# controller.net
KiCad netlist of a schematic drawn in EAGLE
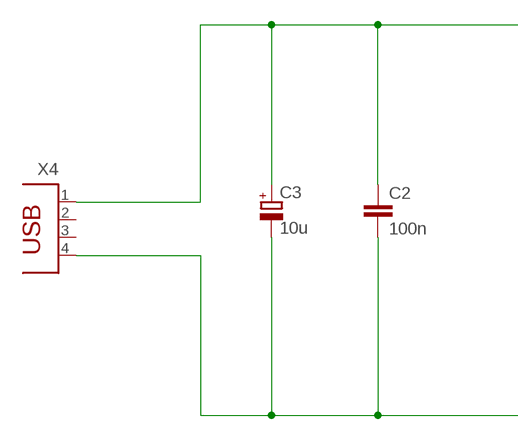
[diagram p0: schematic, sheet 1, part 1 of 2]
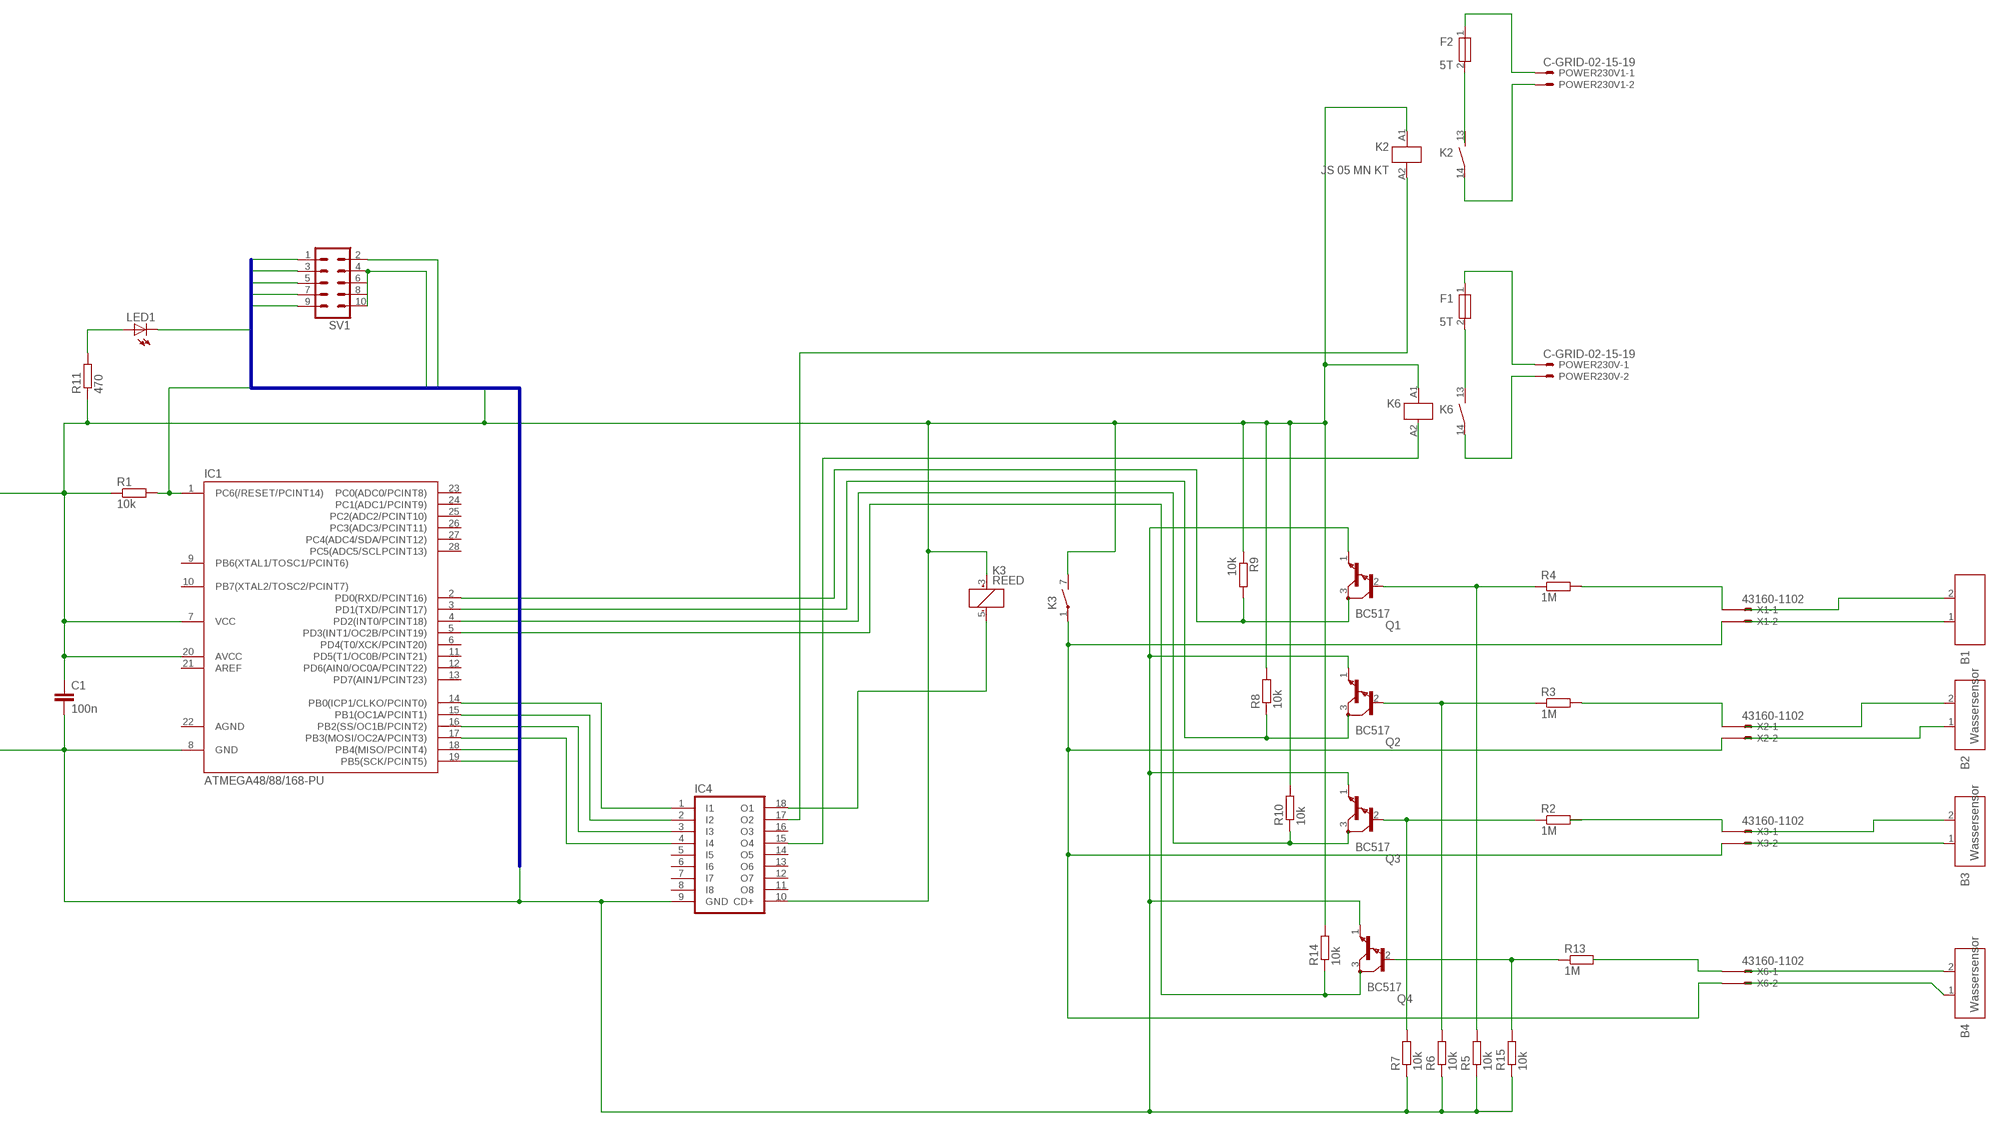
[diagram p1: schematic, sheet 1, part 2 of 2]

(export (version "E")
  (design (tool "Eeschema 10.0.6"))
  (components
    (comp (ref "B1")
      (value "MESSFUEHLER_2")
      (footprint "eagle-import:MESSFUEHLER_2")
      (fields (field (name "FUNKTION") "Wassersensor"))
      (libsource (lib "eagle-import") (part "MESSFUEHLER_2"))
    )
    (comp (ref "B2")
      (value "MESSFUEHLER_2")
      (footprint "eagle-import:MESSFUEHLER_2")
      (fields (field (name "FUNKTION") "Wassersensor"))
      (libsource (lib "eagle-import") (part "MESSFUEHLER_2"))
    )
    (comp (ref "B3")
      (value "MESSFUEHLER_2")
      (footprint "eagle-import:MESSFUEHLER_2")
      (fields (field (name "FUNKTION") "Wassersensor"))
      (libsource (lib "eagle-import") (part "MESSFUEHLER_2"))
    )
    (comp (ref "B4")
      (value "MESSFUEHLER_2")
      (footprint "eagle-import:MESSFUEHLER_2")
      (fields (field (name "FUNKTION") "Wassersensor"))
      (libsource (lib "eagle-import") (part "MESSFUEHLER_2"))
    )
    (comp (ref "C1")
      (value "100n")
      (footprint "eagle-import:C025-025X050")
      (libsource (lib "eagle-import") (part "C-EU025-025X050"))
    )
    (comp (ref "C2")
      (value "100n")
      (footprint "eagle-import:C025-030X050")
      (libsource (lib "eagle-import") (part "C-EU025-030X050"))
    )
    (comp (ref "C3")
      (value "10u")
      (footprint "eagle-import:E2,5-7")
      (libsource (lib "eagle-import") (part "CPOL-EUE2.5-7"))
    )
    (comp (ref "F1")
      (value "SICHERUNG_1-POL")
      (footprint "eagle-import:SICHERUNG_1-POL")
      (fields (field (name "TYPE") "5T"))
      (libsource (lib "eagle-import") (part "SICHERUNG_1-POL"))
    )
    (comp (ref "F2")
      (value "SICHERUNG_1-POL")
      (footprint "eagle-import:SICHERUNG_1-POL")
      (fields (field (name "TYPE") "5T"))
      (libsource (lib "eagle-import") (part "SICHERUNG_1-POL"))
    )
    (comp (ref "IC1")
      (value "ATMEGA48/88/168-PU")
      (footprint "eagle-import:DIL28-3")
      (libsource (lib "eagle-import") (part "ATMEGA48/88/168-PU"))
    )
    (comp (ref "IC4")
      (value "ULN2803A")
      (footprint "eagle-import:DIL18")
      (libsource (lib "eagle-import") (part "ULN2803A"))
    )
    (comp (ref "K2")
      (value "HILFSSCHUETZ_13-14")
      (footprint "eagle-import:HILFSSCHUETZ_13-14")
      (fields (field (name "TYPE") "JS 05 MN KT"))
      (libsource (lib "eagle-import") (part "HILFSSCHUETZ_13-14"))
    )
    (comp (ref "K3")
      (value "REED")
      (footprint "eagle-import:REED")
      (libsource (lib "eagle-import") (part "REED"))
    )
    (comp (ref "K6")
      (value "HILFSSCHUETZ_13-14")
      (footprint "eagle-import:HILFSSCHUETZ_13-14")
      (fields (field (name "TYPE") "JS 05 MN KT"))
      (libsource (lib "eagle-import") (part "HILFSSCHUETZ_13-14"))
    )
    (comp (ref "LED1")
      (value "LED5MM")
      (footprint "eagle-import:LED5MM")
      (libsource (lib "eagle-import") (part "LED5MM"))
    )
    (comp (ref "POWER230V")
      (value "C-GRID-02-15-19")
      (footprint "eagle-import:15-91-02")
      (libsource (lib "eagle-import") (part "C-GRID-02-15-19"))
    )
    (comp (ref "POWER230V1")
      (value "C-GRID-02-15-19")
      (footprint "eagle-import:15-91-02")
      (libsource (lib "eagle-import") (part "C-GRID-02-15-19"))
    )
    (comp (ref "Q1")
      (value "BC517")
      (footprint "eagle-import:TO92")
      (libsource (lib "eagle-import") (part "BC517"))
    )
    (comp (ref "Q2")
      (value "BC517")
      (footprint "eagle-import:TO92")
      (libsource (lib "eagle-import") (part "BC517"))
    )
    (comp (ref "Q3")
      (value "BC517")
      (footprint "eagle-import:TO92")
      (libsource (lib "eagle-import") (part "BC517"))
    )
    (comp (ref "Q4")
      (value "BC517")
      (footprint "eagle-import:TO92")
      (libsource (lib "eagle-import") (part "BC517"))
    )
    (comp (ref "R1")
      (value "10k")
      (footprint "eagle-import:0204_7")
      (libsource (lib "eagle-import") (part "R-EU_0204/7"))
    )
    (comp (ref "R2")
      (value "1M")
      (footprint "eagle-import:0204_7")
      (libsource (lib "eagle-import") (part "R-EU_0204/7"))
    )
    (comp (ref "R3")
      (value "1M")
      (footprint "eagle-import:0204_7")
      (libsource (lib "eagle-import") (part "R-EU_0204/7"))
    )
    (comp (ref "R4")
      (value "1M")
      (footprint "eagle-import:0204_7")
      (libsource (lib "eagle-import") (part "R-EU_0204/7"))
    )
    (comp (ref "R5")
      (value "10k")
      (footprint "eagle-import:0204_7")
      (libsource (lib "eagle-import") (part "R-EU_0204/7"))
    )
    (comp (ref "R6")
      (value "10k")
      (footprint "eagle-import:0204_7")
      (libsource (lib "eagle-import") (part "R-EU_0204/7"))
    )
    (comp (ref "R7")
      (value "10k")
      (footprint "eagle-import:0204_7")
      (libsource (lib "eagle-import") (part "R-EU_0204/7"))
    )
    (comp (ref "R8")
      (value "10k")
      (footprint "eagle-import:0204_7")
      (libsource (lib "eagle-import") (part "R-EU_0204/7"))
    )
    (comp (ref "R9")
      (value "10k")
      (footprint "eagle-import:0204_7")
      (libsource (lib "eagle-import") (part "R-EU_0204/7"))
    )
    (comp (ref "R10")
      (value "10k")
      (footprint "eagle-import:0204_7")
      (libsource (lib "eagle-import") (part "R-EU_0204/7"))
    )
    (comp (ref "R11")
      (value "470")
      (footprint "eagle-import:0204_7")
      (libsource (lib "eagle-import") (part "R-EU_0204/7"))
    )
    (comp (ref "R13")
      (value "1M")
      (footprint "eagle-import:0204_7")
      (libsource (lib "eagle-import") (part "R-EU_0204/7"))
    )
    (comp (ref "R14")
      (value "10k")
      (footprint "eagle-import:0204_7")
      (libsource (lib "eagle-import") (part "R-EU_0204/7"))
    )
    (comp (ref "R15")
      (value "10k")
      (footprint "eagle-import:0204_7")
      (libsource (lib "eagle-import") (part "R-EU_0204/7"))
    )
    (comp (ref "SV1")
      (value "MA05-2")
      (footprint "eagle-import:MA05-2")
      (libsource (lib "eagle-import") (part "MA05-2"))
    )
    (comp (ref "X1")
      (value "43160-1102")
      (footprint "eagle-import:43160-XX02")
      (fields (field (name "MF") "WALDOM/MOLEX"))
      (libsource (lib "eagle-import") (part "43160-0211"))
    )
    (comp (ref "X2")
      (value "43160-1102")
      (footprint "eagle-import:43160-XX02")
      (fields (field (name "MF") "WALDOM/MOLEX"))
      (libsource (lib "eagle-import") (part "43160-0211"))
    )
    (comp (ref "X3")
      (value "43160-1102")
      (footprint "eagle-import:43160-XX02")
      (fields (field (name "MF") "WALDOM/MOLEX"))
      (libsource (lib "eagle-import") (part "43160-0211"))
    )
    (comp (ref "X4")
      (value "PN87520")
      (footprint "eagle-import:PN87520")
      (libsource (lib "eagle-import") (part "PN87520"))
    )
    (comp (ref "X6")
      (value "43160-1102")
      (footprint "eagle-import:43160-XX02")
      (fields (field (name "MF") "WALDOM/MOLEX"))
      (libsource (lib "eagle-import") (part "43160-0211"))
    )
  )
  (nets
    (net (code "1") (name "/AGND") (class "Default")
      (node (ref "IC1") (pin "22") (pinfunction "AGND_22") (pintype "power_in"))
    )
    (net (code "2") (name "/GND") (class "Default")
      (node (ref "C1") (pin "2") (pinfunction "2_2") (pintype "passive"))
      (node (ref "C2") (pin "2") (pinfunction "2_2") (pintype "passive"))
      (node (ref "C3") (pin "-") (pinfunction "-_-") (pintype "passive"))
      (node (ref "IC1") (pin "8") (pinfunction "GND_8") (pintype "power_in"))
      (node (ref "IC4") (pin "9") (pinfunction "GND_9") (pintype "power_in"))
      (node (ref "Q1") (pin "1") (pinfunction "E_1") (pintype "passive"))
      (node (ref "Q2") (pin "1") (pinfunction "E_1") (pintype "passive"))
      (node (ref "Q3") (pin "1") (pinfunction "E_1") (pintype "passive"))
      (node (ref "Q4") (pin "1") (pinfunction "E_1") (pintype "passive"))
      (node (ref "R15") (pin "1") (pinfunction "1_1") (pintype "passive"))
      (node (ref "R5") (pin "1") (pinfunction "1_1") (pintype "passive"))
      (node (ref "R6") (pin "1") (pinfunction "1_1") (pintype "passive"))
      (node (ref "R7") (pin "1") (pinfunction "1_1") (pintype "passive"))
      (node (ref "SV1") (pin "10") (pinfunction "10_10") (pintype "passive"))
      (node (ref "SV1") (pin "2") (pinfunction "2_2") (pintype "passive"))
      (node (ref "SV1") (pin "4") (pinfunction "4_4") (pintype "passive"))
      (node (ref "X4") (pin "4") (pinfunction "4_4") (pintype "passive"))
    )
    (net (code "3") (name "/LED") (class "Default")
      (node (ref "LED1") (pin "K") (pinfunction "C_K") (pintype "passive"))
      (node (ref "SV1") (pin "3") (pinfunction "3_3") (pintype "passive"))
    )
    (net (code "4") (name "/MISO") (class "Default")
      (node (ref "IC1") (pin "18") (pinfunction "PB4(MISO/PCINT4)_18") (pintype "bidirectional"))
      (node (ref "SV1") (pin "9") (pinfunction "9_9") (pintype "passive"))
    )
    (net (code "5") (name "/MOSI") (class "Default")
      (node (ref "IC1") (pin "17") (pinfunction "PB3(MOSI/OC2A/PCINT3)_17") (pintype "bidirectional"))
      (node (ref "IC4") (pin "4") (pinfunction "I4_4") (pintype "input"))
      (node (ref "SV1") (pin "1") (pinfunction "1_1") (pintype "passive"))
    )
    (net (code "6") (name "/RESET") (class "Default")
      (node (ref "IC1") (pin "1") (pinfunction "PC6(/RESET/PCINT14)_1") (pintype "bidirectional"))
      (node (ref "R1") (pin "2") (pinfunction "2_2") (pintype "passive"))
      (node (ref "SV1") (pin "5") (pinfunction "5_5") (pintype "passive"))
    )
    (net (code "7") (name "/SCK") (class "Default")
      (node (ref "IC1") (pin "19") (pinfunction "PB5(SCK/PCINT5)_19") (pintype "bidirectional"))
      (node (ref "SV1") (pin "7") (pinfunction "7_7") (pintype "passive"))
    )
    (net (code "8") (name "Net-(IC1-AVCC)") (class "Default")
      (node (ref "C1") (pin "1") (pinfunction "1_1") (pintype "passive"))
      (node (ref "C2") (pin "1") (pinfunction "1_1") (pintype "passive"))
      (node (ref "C3") (pin "+") (pinfunction "+_+") (pintype "passive"))
      (node (ref "IC1") (pin "20") (pinfunction "AVCC_20") (pintype "passive"))
      (node (ref "IC1") (pin "7") (pinfunction "VCC_7") (pintype "power_in"))
      (node (ref "IC4") (pin "10") (pinfunction "CD+_10") (pintype "passive"))
      (node (ref "K2") (pin "A1") (pinfunction "A1_A1") (pintype "input"))
      (node (ref "K3") (pin "3") (pinfunction "+_3") (pintype "passive"))
      (node (ref "K3") (pin "7") (pinfunction "S_7") (pintype "passive"))
      (node (ref "K6") (pin "A1") (pinfunction "A1_A1") (pintype "input"))
      (node (ref "R1") (pin "1") (pinfunction "1_1") (pintype "passive"))
      (node (ref "R10") (pin "2") (pinfunction "2_2") (pintype "passive"))
      (node (ref "R11") (pin "1") (pinfunction "1_1") (pintype "passive"))
      (node (ref "R14") (pin "2") (pinfunction "2_2") (pintype "passive"))
      (node (ref "R8") (pin "2") (pinfunction "2_2") (pintype "passive"))
      (node (ref "R9") (pin "1") (pinfunction "1_1") (pintype "passive"))
      (node (ref "X4") (pin "1") (pinfunction "1_1") (pintype "passive"))
    )
    (net (code "9") (name "Net-(IC1-PB0(ICP1{slash}CLKO{slash}PCINT0))") (class "Default")
      (node (ref "IC1") (pin "14") (pinfunction "PB0(ICP1/CLKO/PCINT0)_14") (pintype "bidirectional"))
      (node (ref "IC4") (pin "1") (pinfunction "I1_1") (pintype "input"))
    )
    (net (code "10") (name "Net-(IC1-PB1(OC1A{slash}PCINT1))") (class "Default")
      (node (ref "IC1") (pin "15") (pinfunction "PB1(OC1A/PCINT1)_15") (pintype "bidirectional"))
      (node (ref "IC4") (pin "2") (pinfunction "I2_2") (pintype "input"))
    )
    (net (code "11") (name "Net-(IC1-PB2(SS{slash}OC1B{slash}PCINT2))") (class "Default")
      (node (ref "IC1") (pin "16") (pinfunction "PB2(SS/OC1B/PCINT2)_16") (pintype "bidirectional"))
      (node (ref "IC4") (pin "3") (pinfunction "I3_3") (pintype "input"))
    )
    (net (code "12") (name "Net-(IC1-PD0(RXD{slash}PCINT16))") (class "Default")
      (node (ref "IC1") (pin "2") (pinfunction "PD0(RXD/PCINT16)_2") (pintype "bidirectional"))
      (node (ref "Q1") (pin "3") (pinfunction "C_3") (pintype "passive"))
      (node (ref "R9") (pin "2") (pinfunction "2_2") (pintype "passive"))
    )
    (net (code "13") (name "Net-(IC1-PD1(TXD{slash}PCINT17))") (class "Default")
      (node (ref "IC1") (pin "3") (pinfunction "PD1(TXD/PCINT17)_3") (pintype "bidirectional"))
      (node (ref "Q2") (pin "3") (pinfunction "C_3") (pintype "passive"))
      (node (ref "R8") (pin "1") (pinfunction "1_1") (pintype "passive"))
    )
    (net (code "14") (name "Net-(IC1-PD2(INT0{slash}PCINT18))") (class "Default")
      (node (ref "IC1") (pin "4") (pinfunction "PD2(INT0/PCINT18)_4") (pintype "bidirectional"))
      (node (ref "Q3") (pin "3") (pinfunction "C_3") (pintype "passive"))
      (node (ref "R10") (pin "1") (pinfunction "1_1") (pintype "passive"))
    )
    (net (code "15") (name "Net-(IC1-PD3(INT1{slash}OC2B{slash}PCINT19))") (class "Default")
      (node (ref "IC1") (pin "5") (pinfunction "PD3(INT1/OC2B/PCINT19)_5") (pintype "bidirectional"))
      (node (ref "Q4") (pin "3") (pinfunction "C_3") (pintype "passive"))
      (node (ref "R14") (pin "1") (pinfunction "1_1") (pintype "passive"))
    )
    (net (code "16") (name "Net-(IC4-O1)") (class "Default")
      (node (ref "IC4") (pin "18") (pinfunction "O1_18") (pintype "open_collector"))
      (node (ref "K3") (pin "5") (pinfunction "-_5") (pintype "passive"))
    )
    (net (code "17") (name "Net-(IC4-O2)") (class "Default")
      (node (ref "IC4") (pin "17") (pinfunction "O2_17") (pintype "open_collector"))
      (node (ref "K2") (pin "A2") (pinfunction "A2_A2") (pintype "input"))
    )
    (net (code "18") (name "Net-(K2A-4)") (class "Default")
      (node (ref "K2") (pin "14") (pinfunction "4_14") (pintype "passive"))
      (node (ref "POWER230V1") (pin "2") (pinfunction "S_2") (pintype "passive"))
    )
    (net (code "19") (name "Net-(K3B-P)") (class "Default")
      (node (ref "K3") (pin "1") (pinfunction "P_1") (pintype "passive"))
      (node (ref "X1") (pin "2@1") (pinfunction "S_2@1") (pintype "passive"))
      (node (ref "X2") (pin "2@1") (pinfunction "S_2@1") (pintype "passive"))
      (node (ref "X3") (pin "2@1") (pinfunction "S_2@1") (pintype "passive"))
      (node (ref "X6") (pin "2@1") (pinfunction "S_2@1") (pintype "passive"))
    )
    (net (code "20") (name "Net-(K6A-3)") (class "Default")
      (node (ref "F1") (pin "2") (pinfunction "2_2") (pintype "passive"))
      (node (ref "K6") (pin "13") (pinfunction "3_13") (pintype "passive"))
    )
    (net (code "21") (name "Net-(K6A-4)") (class "Default")
      (node (ref "K6") (pin "14") (pinfunction "4_14") (pintype "passive"))
      (node (ref "POWER230V") (pin "2") (pinfunction "S_2") (pintype "passive"))
    )
    (net (code "22") (name "Net-(LED1-PadA)") (class "Default")
      (node (ref "LED1") (pin "A") (pinfunction "A_A") (pintype "passive"))
      (node (ref "R11") (pin "2") (pinfunction "2_2") (pintype "passive"))
    )
    (net (code "23") (name "Net-(POWER230V1A-S)") (class "Default")
      (node (ref "F2") (pin "1") (pinfunction "1_1") (pintype "passive"))
      (node (ref "POWER230V1") (pin "1") (pinfunction "S_1") (pintype "passive"))
    )
    (net (code "24") (name "Net-(POWER230VA-S)") (class "Default")
      (node (ref "F1") (pin "1") (pinfunction "1_1") (pintype "passive"))
      (node (ref "POWER230V") (pin "1") (pinfunction "S_1") (pintype "passive"))
    )
    (net (code "25") (name "Net-(Q1-B)") (class "Default")
      (node (ref "Q1") (pin "2") (pinfunction "B_2") (pintype "passive"))
      (node (ref "R4") (pin "1") (pinfunction "1_1") (pintype "passive"))
      (node (ref "R5") (pin "2") (pinfunction "2_2") (pintype "passive"))
    )
    (net (code "26") (name "Net-(Q2-B)") (class "Default")
      (node (ref "Q2") (pin "2") (pinfunction "B_2") (pintype "passive"))
      (node (ref "R3") (pin "1") (pinfunction "1_1") (pintype "passive"))
      (node (ref "R6") (pin "2") (pinfunction "2_2") (pintype "passive"))
    )
    (net (code "27") (name "Net-(Q3-B)") (class "Default")
      (node (ref "Q3") (pin "2") (pinfunction "B_2") (pintype "passive"))
      (node (ref "R2") (pin "1") (pinfunction "1_1") (pintype "passive"))
      (node (ref "R7") (pin "2") (pinfunction "2_2") (pintype "passive"))
    )
    (net (code "28") (name "Net-(Q4-B)") (class "Default")
      (node (ref "Q4") (pin "2") (pinfunction "B_2") (pintype "passive"))
      (node (ref "R13") (pin "1") (pinfunction "1_1") (pintype "passive"))
      (node (ref "R15") (pin "2") (pinfunction "2_2") (pintype "passive"))
    )
    (net (code "29") (name "Net-(R2-Pad2)") (class "Default")
      (node (ref "R2") (pin "2") (pinfunction "2_2") (pintype "passive"))
      (node (ref "X3") (pin "1@1") (pinfunction "S_1@1") (pintype "passive"))
    )
    (net (code "30") (name "Net-(R3-Pad2)") (class "Default")
      (node (ref "R3") (pin "2") (pinfunction "2_2") (pintype "passive"))
      (node (ref "X2") (pin "1@1") (pinfunction "S_1@1") (pintype "passive"))
    )
    (net (code "31") (name "Net-(R4-Pad2)") (class "Default")
      (node (ref "R4") (pin "2") (pinfunction "2_2") (pintype "passive"))
      (node (ref "X1") (pin "1@1") (pinfunction "S_1@1") (pintype "passive"))
    )
    (net (code "32") (name "unconnected-(B1-Pad1)") (class "Default")
      (node (ref "B1") (pin "1") (pinfunction "1_1") (pintype "passive"))
    )
    (net (code "33") (name "unconnected-(B1-Pad2)") (class "Default")
      (node (ref "B1") (pin "2") (pinfunction "2_2") (pintype "passive"))
    )
    (net (code "34") (name "unconnected-(B2-Pad1)") (class "Default")
      (node (ref "B2") (pin "1") (pinfunction "1_1") (pintype "passive"))
    )
    (net (code "35") (name "unconnected-(B2-Pad2)") (class "Default")
      (node (ref "B2") (pin "2") (pinfunction "2_2") (pintype "passive"))
    )
    (net (code "36") (name "unconnected-(B3-Pad1)") (class "Default")
      (node (ref "B3") (pin "1") (pinfunction "1_1") (pintype "passive"))
    )
    (net (code "37") (name "unconnected-(B3-Pad2)") (class "Default")
      (node (ref "B3") (pin "2") (pinfunction "2_2") (pintype "passive"))
    )
    (net (code "38") (name "unconnected-(B4-Pad1)") (class "Default")
      (node (ref "B4") (pin "1") (pinfunction "1_1") (pintype "passive"))
    )
    (net (code "39") (name "unconnected-(B4-Pad2)") (class "Default")
      (node (ref "B4") (pin "2") (pinfunction "2_2") (pintype "passive"))
    )
    (net (code "40") (name "unconnected-(F2-Pad2)") (class "Default")
      (node (ref "F2") (pin "2") (pinfunction "2_2") (pintype "passive"))
    )
    (net (code "41") (name "unconnected-(IC1-AREF-Pad21)") (class "Default")
      (node (ref "IC1") (pin "21") (pinfunction "AREF_21") (pintype "passive"))
    )
    (net (code "42") (name "unconnected-(IC1-PB6(XTAL1{slash}TOSC1{slash}PCINT6)-Pad9)") (class "Default")
      (node (ref "IC1") (pin "9") (pinfunction "PB6(XTAL1/TOSC1/PCINT6)_9") (pintype "bidirectional"))
    )
    (net (code "43") (name "unconnected-(IC1-PB7(XTAL2{slash}TOSC2{slash}PCINT7)-Pad10)") (class "Default")
      (node (ref "IC1") (pin "10") (pinfunction "PB7(XTAL2/TOSC2/PCINT7)_10") (pintype "bidirectional"))
    )
    (net (code "44") (name "unconnected-(IC1-PC0(ADC0{slash}PCINT8)-Pad23)") (class "Default")
      (node (ref "IC1") (pin "23") (pinfunction "PC0(ADC0/PCINT8)_23") (pintype "bidirectional"))
    )
    (net (code "45") (name "unconnected-(IC1-PC1(ADC1{slash}PCINT9)-Pad24)") (class "Default")
      (node (ref "IC1") (pin "24") (pinfunction "PC1(ADC1/PCINT9)_24") (pintype "bidirectional"))
    )
    (net (code "46") (name "unconnected-(IC1-PC2(ADC2{slash}PCINT10)-Pad25)") (class "Default")
      (node (ref "IC1") (pin "25") (pinfunction "PC2(ADC2/PCINT10)_25") (pintype "bidirectional"))
    )
    (net (code "47") (name "unconnected-(IC1-PC3(ADC3{slash}PCINT11)-Pad26)") (class "Default")
      (node (ref "IC1") (pin "26") (pinfunction "PC3(ADC3/PCINT11)_26") (pintype "bidirectional"))
    )
    (net (code "48") (name "unconnected-(IC1-PC4(ADC4{slash}SDA{slash}PCINT12)-Pad27)") (class "Default")
      (node (ref "IC1") (pin "27") (pinfunction "PC4(ADC4/SDA/PCINT12)_27") (pintype "bidirectional"))
    )
    (net (code "49") (name "unconnected-(IC1-PC5(ADC5{slash}SCLPCINT13)-Pad28)") (class "Default")
      (node (ref "IC1") (pin "28") (pinfunction "PC5(ADC5/SCLPCINT13)_28") (pintype "bidirectional"))
    )
    (net (code "50") (name "unconnected-(IC1-PD4(T0{slash}XCK{slash}PCINT20)-Pad6)") (class "Default")
      (node (ref "IC1") (pin "6") (pinfunction "PD4(T0/XCK/PCINT20)_6") (pintype "bidirectional"))
    )
    (net (code "51") (name "unconnected-(IC1-PD5(T1{slash}OC0B{slash}PCINT21)-Pad11)") (class "Default")
      (node (ref "IC1") (pin "11") (pinfunction "PD5(T1/OC0B/PCINT21)_11") (pintype "bidirectional"))
    )
    (net (code "52") (name "unconnected-(IC1-PD6(AIN0{slash}OC0A{slash}PCINT22)-Pad12)") (class "Default")
      (node (ref "IC1") (pin "12") (pinfunction "PD6(AIN0/OC0A/PCINT22)_12") (pintype "bidirectional"))
    )
    (net (code "53") (name "unconnected-(IC1-PD7(AIN1{slash}PCINT23)-Pad13)") (class "Default")
      (node (ref "IC1") (pin "13") (pinfunction "PD7(AIN1/PCINT23)_13") (pintype "bidirectional"))
    )
    (net (code "54") (name "unconnected-(IC4-I5-Pad5)") (class "Default")
      (node (ref "IC4") (pin "5") (pinfunction "I5_5") (pintype "input"))
    )
    (net (code "55") (name "unconnected-(IC4-I6-Pad6)") (class "Default")
      (node (ref "IC4") (pin "6") (pinfunction "I6_6") (pintype "input"))
    )
    (net (code "56") (name "unconnected-(IC4-I7-Pad7)") (class "Default")
      (node (ref "IC4") (pin "7") (pinfunction "I7_7") (pintype "input"))
    )
    (net (code "57") (name "unconnected-(IC4-I8-Pad8)") (class "Default")
      (node (ref "IC4") (pin "8") (pinfunction "I8_8") (pintype "input"))
    )
    (net (code "58") (name "unconnected-(IC4-O3-Pad16)") (class "Default")
      (node (ref "IC4") (pin "16") (pinfunction "O3_16") (pintype "open_collector"))
    )
    (net (code "59") (name "unconnected-(IC4-O4-Pad15)") (class "Default")
      (node (ref "IC4") (pin "15") (pinfunction "O4_15") (pintype "open_collector"))
    )
    (net (code "60") (name "unconnected-(IC4-O5-Pad14)") (class "Default")
      (node (ref "IC4") (pin "14") (pinfunction "O5_14") (pintype "open_collector"))
    )
    (net (code "61") (name "unconnected-(IC4-O6-Pad13)") (class "Default")
      (node (ref "IC4") (pin "13") (pinfunction "O6_13") (pintype "open_collector"))
    )
    (net (code "62") (name "unconnected-(IC4-O7-Pad12)") (class "Default")
      (node (ref "IC4") (pin "12") (pinfunction "O7_12") (pintype "open_collector"))
    )
    (net (code "63") (name "unconnected-(IC4-O8-Pad11)") (class "Default")
      (node (ref "IC4") (pin "11") (pinfunction "O8_11") (pintype "open_collector"))
    )
    (net (code "64") (name "unconnected-(K2A-3-Pad13)") (class "Default")
      (node (ref "K2") (pin "13") (pinfunction "3_13") (pintype "passive"))
    )
    (net (code "65") (name "unconnected-(K6-PadA2)") (class "Default")
      (node (ref "K6") (pin "A2") (pinfunction "A2_A2") (pintype "input"))
    )
    (net (code "66") (name "unconnected-(R13-Pad2)") (class "Default")
      (node (ref "R13") (pin "2") (pinfunction "2_2") (pintype "passive"))
    )
    (net (code "67") (name "unconnected-(SV1-Pad6)") (class "Default")
      (node (ref "SV1") (pin "6") (pinfunction "6_6") (pintype "passive"))
    )
    (net (code "68") (name "unconnected-(SV1-Pad8)") (class "Default")
      (node (ref "SV1") (pin "8") (pinfunction "8_8") (pintype "passive"))
    )
    (net (code "69") (name "unconnected-(X1A-S-Pad1@2)") (class "Default")
      (node (ref "X1") (pin "1@2") (pinfunction "S_1@2") (pintype "passive"))
    )
    (net (code "70") (name "unconnected-(X1B-S-Pad2@2)") (class "Default")
      (node (ref "X1") (pin "2@2") (pinfunction "S_2@2") (pintype "passive"))
    )
    (net (code "71") (name "unconnected-(X2A-S-Pad1@2)") (class "Default")
      (node (ref "X2") (pin "1@2") (pinfunction "S_1@2") (pintype "passive"))
    )
    (net (code "72") (name "unconnected-(X2B-S-Pad2@2)") (class "Default")
      (node (ref "X2") (pin "2@2") (pinfunction "S_2@2") (pintype "passive"))
    )
    (net (code "73") (name "unconnected-(X3A-S-Pad1@2)") (class "Default")
      (node (ref "X3") (pin "1@2") (pinfunction "S_1@2") (pintype "passive"))
    )
    (net (code "74") (name "unconnected-(X3B-S-Pad2@2)") (class "Default")
      (node (ref "X3") (pin "2@2") (pinfunction "S_2@2") (pintype "passive"))
    )
    (net (code "75") (name "unconnected-(X4-Pad2)") (class "Default")
      (node (ref "X4") (pin "2") (pinfunction "2_2") (pintype "passive"))
    )
    (net (code "76") (name "unconnected-(X4-Pad3)") (class "Default")
      (node (ref "X4") (pin "3") (pinfunction "3_3") (pintype "passive"))
    )
    (net (code "77") (name "unconnected-(X6A-S-Pad1@1)") (class "Default")
      (node (ref "X6") (pin "1@1") (pinfunction "S_1@1") (pintype "passive"))
    )
    (net (code "78") (name "unconnected-(X6A-S-Pad1@2)") (class "Default")
      (node (ref "X6") (pin "1@2") (pinfunction "S_1@2") (pintype "passive"))
    )
    (net (code "79") (name "unconnected-(X6B-S-Pad2@2)") (class "Default")
      (node (ref "X6") (pin "2@2") (pinfunction "S_2@2") (pintype "passive"))
    )
  )
)
